# Trip_Detector.net
KiCad netlist of a schematic drawn in Altium Designer
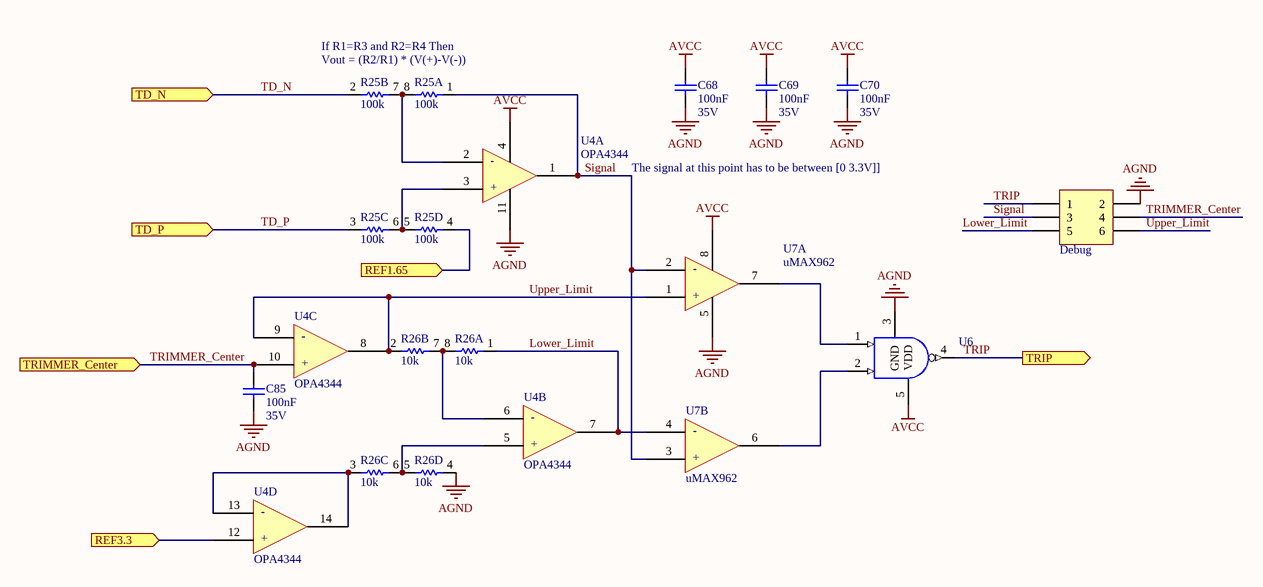
[diagram p0: Trip Detector.SchDoc]

(export (version "E")
  (design (tool "Eeschema 10.0.6"))
  (components
    (comp (ref "C68")
      (value "100nF")
      (footprint "CAP_0603")
      (description "Capacitor")
      (fields
        (field (name "MPN") "C0603C104M5RACTU")
        (field (name "MF") "KEMET")
        (field (name "VOLTAGE") "35V")
        (field (name "PUBLISHER") "Altium Limited")
      )
      (libsource (lib "Componentes_SOC") (part "Cap_0603"))
    )
    (comp (ref "C69")
      (value "100nF")
      (footprint "CAP_0603")
      (description "Capacitor")
      (fields
        (field (name "MPN") "C0603C104M5RACTU")
        (field (name "MF") "KEMET")
        (field (name "VOLTAGE") "35V")
        (field (name "PUBLISHER") "Altium Limited")
      )
      (libsource (lib "Componentes_SOC") (part "Cap_0603"))
    )
    (comp (ref "C70")
      (value "100nF")
      (footprint "CAP_0603")
      (description "Capacitor")
      (fields
        (field (name "MPN") "C0603C104M5RACTU")
        (field (name "MF") "KEMET")
        (field (name "VOLTAGE") "35V")
        (field (name "PUBLISHER") "Altium Limited")
      )
      (libsource (lib "Componentes_SOC") (part "Cap_0603"))
    )
    (comp (ref "C85")
      (value "100nF")
      (footprint "CAP_0603")
      (description "Capacitor")
      (fields
        (field (name "MPN") "C0603C104M5RACTU")
        (field (name "MF") "KEMET")
        (field (name "VOLTAGE") "35V")
        (field (name "PUBLISHER") "Altium Limited")
      )
      (libsource (lib "Componentes_SOC") (part "Cap_0603"))
    )
    (comp (ref "Debug")
      (value "Connector Header Through Hole, Right Angle 6 position 0.0.79\" (2mm)")
      (footprint "Header 3x2 Macho Pitch 1.27mm")
      (description "Connector Header Through Hole 6 position 0.050\" (1.27mm)")
      (libsource (lib "Componentes_SOC") (part "Header 3x2 Macho_Pitch_1.27mm"))
    )
    (comp (ref "R25")
      (value "100k")
      (footprint "CAC-80P320X160-8N")
      (description "Chip Resistor Array 0606, 4xR")
      (fields (field (name "MANUFACTURER") "Vishay") (field (name "CREATED") "Kreppel_0420"))
      (libsource (lib "Componentes_SOC") (part "ResArray 1206"))
    )
    (comp (ref "R26")
      (value "10k")
      (footprint "CAC-80P320X160-8N")
      (description "Chip Resistor Array 0606, 4xR")
      (fields (field (name "MANUFACTURER") "Vishay") (field (name "CREATED") "Kreppel_0420"))
      (libsource (lib "Componentes_SOC") (part "ResArray 1206"))
    )
    (comp (ref "U4")
      (value "OPA4344")
      (footprint "TSSO5X6-G14/X.3")
      (description "opamp rai to rail 1mV")
      (libsource (lib "Componentes_SOC") (part "OPA4344"))
    )
    (comp (ref "U6")
      (value "MC74VHC1G00DFT1")
      (footprint "SOT-353")
      (description "2-Input NAND Gate")
      (fields (field (name "PUBLISHER") "Altium Limited"))
      (libsource (lib "Componentes_SOC") (part "MC74VHC1G00DFT1"))
    )
    (comp (ref "U7")
      (value "uMAX962")
      (footprint "8-MSOP")
      (description "IC COMPARATOR BTR 8-UMAX")
      (libsource (lib "Componentes_SOC") (part "MAX962"))
    )
  )
  (nets
    (net (code "1") (name "/Lower_Limit") (class "Default")
      (node (ref "Debug") (pin "5") (pinfunction "5_5") (pintype "passive"))
      (node (ref "R26") (pin "1") (pinfunction "1_1") (pintype "passive"))
      (node (ref "U4") (pin "7") (pinfunction "out_b_7") (pintype "passive"))
      (node (ref "U7") (pin "4") (pinfunction "-IN_B_4") (pintype "passive"))
    )
    (net (code "2") (name "/REF1.65") (class "Default")
      (node (ref "R25") (pin "4") (pinfunction "1_4") (pintype "passive"))
    )
    (net (code "3") (name "/REF3.3") (class "Default")
      (node (ref "U4") (pin "12") (pinfunction "+in_d_12") (pintype "passive"))
    )
    (net (code "4") (name "/Signal") (class "Default")
      (node (ref "Debug") (pin "3") (pinfunction "3_3") (pintype "passive"))
      (node (ref "R25") (pin "1") (pinfunction "1_1") (pintype "passive"))
      (node (ref "U4") (pin "1") (pinfunction "out_a_1") (pintype "passive"))
      (node (ref "U7") (pin "2") (pinfunction "-in_a_2") (pintype "passive"))
      (node (ref "U7") (pin "3") (pinfunction "+IN_B_3") (pintype "passive"))
    )
    (net (code "5") (name "/TD_N") (class "Default")
      (node (ref "R25") (pin "2") (pinfunction "1_2") (pintype "passive"))
    )
    (net (code "6") (name "/TD_P") (class "Default")
      (node (ref "R25") (pin "3") (pinfunction "1_3") (pintype "passive"))
    )
    (net (code "7") (name "/TRIMMER_Center") (class "Default")
      (node (ref "C85") (pin "1") (pinfunction "1_1") (pintype "passive"))
      (node (ref "Debug") (pin "4") (pinfunction "4_4") (pintype "passive"))
      (node (ref "U4") (pin "10") (pinfunction "+in_c_10") (pintype "passive"))
    )
    (net (code "8") (name "/TRIP") (class "Default")
      (node (ref "Debug") (pin "1") (pinfunction "1_1") (pintype "passive"))
      (node (ref "U6") (pin "4") (pinfunction "~{Y}_4") (pintype "output"))
    )
    (net (code "9") (name "/Upper_Limit") (class "Default")
      (node (ref "Debug") (pin "6") (pinfunction "6_6") (pintype "passive"))
      (node (ref "R26") (pin "2") (pinfunction "1_2") (pintype "passive"))
      (node (ref "U4") (pin "8") (pinfunction "out_c_8") (pintype "passive"))
      (node (ref "U4") (pin "9") (pinfunction "-in_c_9") (pintype "passive"))
      (node (ref "U7") (pin "1") (pinfunction "+in_a_1") (pintype "passive"))
    )
    (net (code "10") (name "AGND") (class "Default")
      (node (ref "C68") (pin "2") (pinfunction "2_2") (pintype "passive"))
      (node (ref "C69") (pin "2") (pinfunction "2_2") (pintype "passive"))
      (node (ref "C70") (pin "2") (pinfunction "2_2") (pintype "passive"))
      (node (ref "C85") (pin "2") (pinfunction "2_2") (pintype "passive"))
      (node (ref "Debug") (pin "2") (pinfunction "2_2") (pintype "passive"))
      (node (ref "R26") (pin "4") (pinfunction "1_4") (pintype "passive"))
      (node (ref "U4") (pin "11") (pinfunction "v-_11") (pintype "passive"))
      (node (ref "U6") (pin "3") (pinfunction "GND_3") (pintype "power_in"))
      (node (ref "U7") (pin "5") (pinfunction "GND_5") (pintype "passive"))
    )
    (net (code "11") (name "AVCC") (class "Default")
      (node (ref "C68") (pin "1") (pinfunction "1_1") (pintype "passive"))
      (node (ref "C69") (pin "1") (pinfunction "1_1") (pintype "passive"))
      (node (ref "C70") (pin "1") (pinfunction "1_1") (pintype "passive"))
      (node (ref "U4") (pin "4") (pinfunction "v+_4") (pintype "passive"))
      (node (ref "U6") (pin "5") (pinfunction "VDD_5") (pintype "power_in"))
      (node (ref "U7") (pin "8") (pinfunction "VCC_8") (pintype "passive"))
    )
    (net (code "12") (name "Net-(R25A-2)") (class "Default")
      (node (ref "R25") (pin "7") (pinfunction "2_7") (pintype "passive"))
      (node (ref "R25") (pin "8") (pinfunction "2_8") (pintype "passive"))
      (node (ref "U4") (pin "2") (pinfunction "-in_a_2") (pintype "passive"))
    )
    (net (code "13") (name "Net-(R25C-2)") (class "Default")
      (node (ref "R25") (pin "5") (pinfunction "2_5") (pintype "passive"))
      (node (ref "R25") (pin "6") (pinfunction "2_6") (pintype "passive"))
      (node (ref "U4") (pin "3") (pinfunction "+in_a_3") (pintype "passive"))
    )
    (net (code "14") (name "Net-(R26A-2)") (class "Default")
      (node (ref "R26") (pin "7") (pinfunction "2_7") (pintype "passive"))
      (node (ref "R26") (pin "8") (pinfunction "2_8") (pintype "passive"))
      (node (ref "U4") (pin "6") (pinfunction "-in_b_6") (pintype "passive"))
    )
    (net (code "15") (name "Net-(R26C-1)") (class "Default")
      (node (ref "R26") (pin "3") (pinfunction "1_3") (pintype "passive"))
      (node (ref "U4") (pin "13") (pinfunction "-in_d_13") (pintype "passive"))
      (node (ref "U4") (pin "14") (pinfunction "out_d_14") (pintype "passive"))
    )
    (net (code "16") (name "Net-(R26C-2)") (class "Default")
      (node (ref "R26") (pin "5") (pinfunction "2_5") (pintype "passive"))
      (node (ref "R26") (pin "6") (pinfunction "2_6") (pintype "passive"))
      (node (ref "U4") (pin "5") (pinfunction "+in_b_5") (pintype "passive"))
    )
    (net (code "17") (name "Net-(U6-A)") (class "Default")
      (node (ref "U6") (pin "2") (pinfunction "A_2") (pintype "input"))
      (node (ref "U7") (pin "6") (pinfunction "OUT_B_6") (pintype "passive"))
    )
    (net (code "18") (name "Net-(U6-B)") (class "Default")
      (node (ref "U6") (pin "1") (pinfunction "B_1") (pintype "input"))
      (node (ref "U7") (pin "7") (pinfunction "out_a_7") (pintype "passive"))
    )
  )
)
